# Keyboard_Mouse_Card.net
KiCad netlist of a schematic drawn in Altium Designer
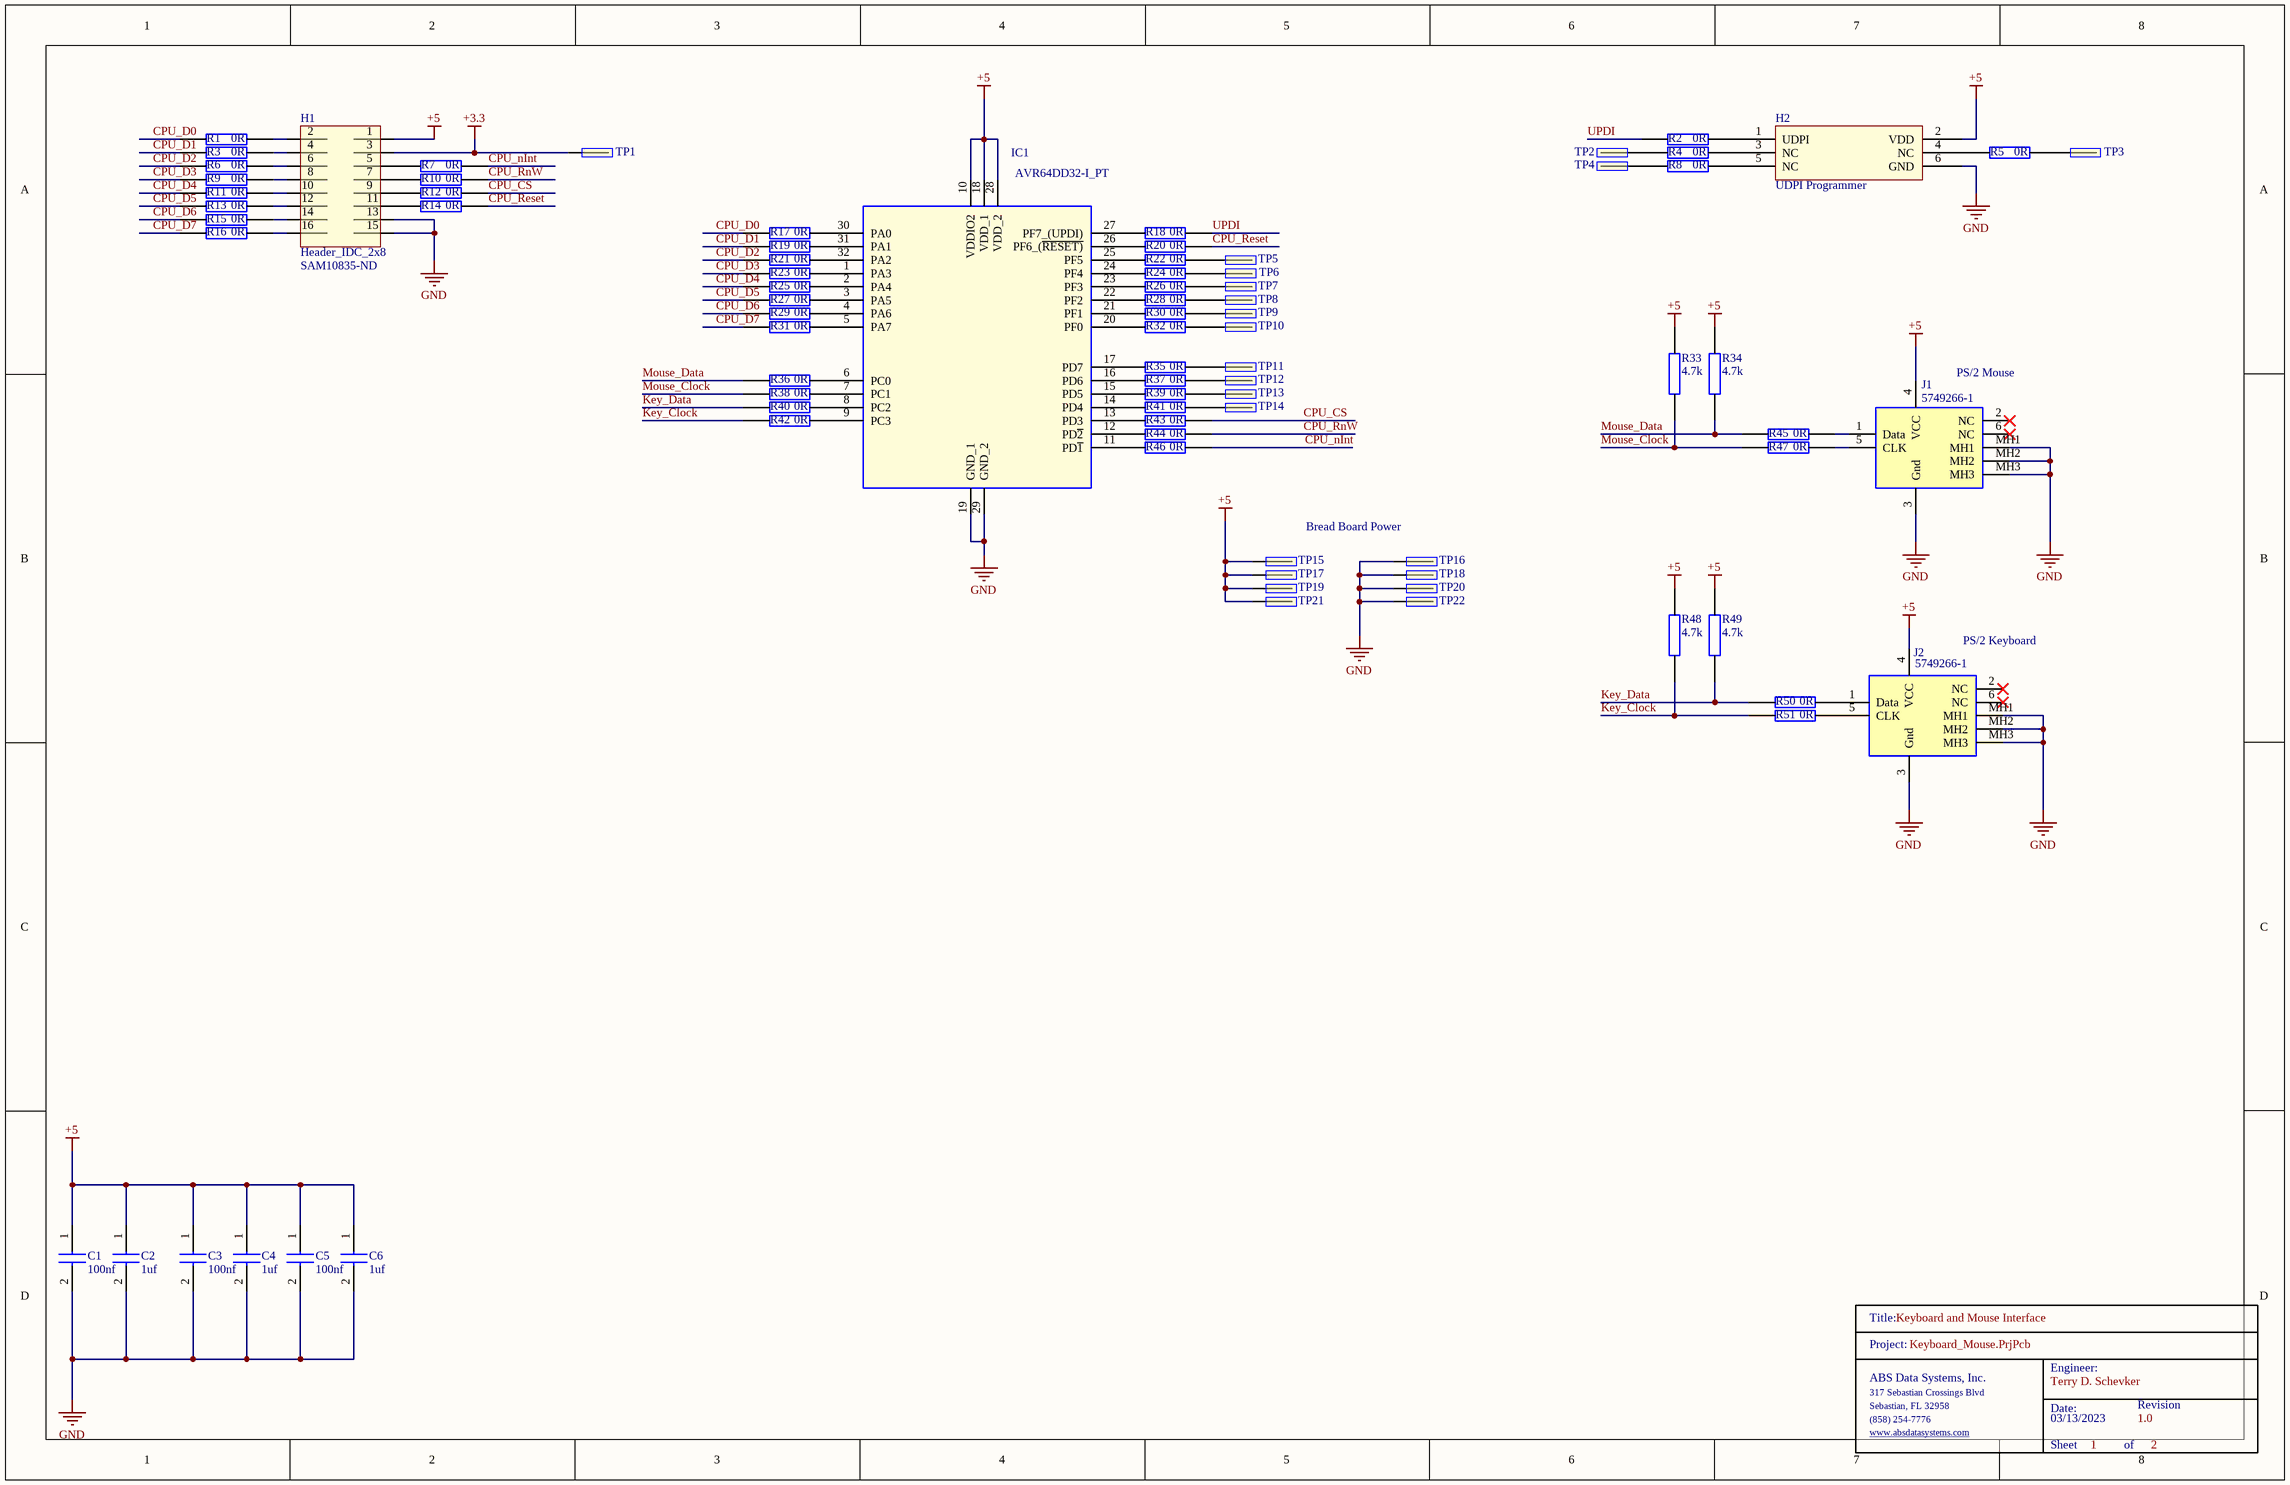
[diagram p0: Keyboard_Mouse_Card.SchDoc]

(export (version "E")
  (design (tool "Eeschema 10.0.6"))
  (components
    (comp (ref "C1")
      (value "100nf")
      (footprint "0603")
      (description "Samsung Electro-Mechanics 0603 100nf")
      (libsource (lib "Capacitors") (part "CL10B104JB8NNNC"))
    )
    (comp (ref "C2")
      (value "1uf")
      (footprint "0603")
      (description "Samsung Electro-Mechanics 0603 1uf")
      (libsource (lib "Capacitors") (part "CL10B105KA8NNNL"))
    )
    (comp (ref "C3")
      (value "100nf")
      (footprint "0603")
      (description "Samsung Electro-Mechanics 0603 100nf")
      (libsource (lib "Capacitors") (part "CL10B104JB8NNNC"))
    )
    (comp (ref "C4")
      (value "1uf")
      (footprint "0603")
      (description "Samsung Electro-Mechanics 0603 1uf")
      (libsource (lib "Capacitors") (part "CL10B105KA8NNNL"))
    )
    (comp (ref "C5")
      (value "100nf")
      (footprint "0603")
      (description "Samsung Electro-Mechanics 0603 100nf")
      (libsource (lib "Capacitors") (part "CL10B104JB8NNNC"))
    )
    (comp (ref "C6")
      (value "1uf")
      (footprint "0603")
      (description "Samsung Electro-Mechanics 0603 1uf")
      (libsource (lib "Capacitors") (part "CL10B105KA8NNNL"))
    )
    (comp (ref "H1")
      (value "Header_IDC_2x8")
      (footprint "HEADER16")
      (description "16 Pin 2x8 Through Hold IDC Connector")
      (fields
        (field (name "MANUFACTURER") "Samtec")
        (field (name "MANUFACTURER PART NUMBER") "TST-108-01-G-D")
        (field (name "SUPPLIER PART NUMBER 1") "SAM10835-ND")
      )
      (libsource (lib "Misc") (part "Header_IDC_2x8"))
    )
    (comp (ref "H2")
      (value "UDPI Programmer")
      (footprint "HDR2X3")
      (description "6 Pin 2X3 Through Hole Header")
      (libsource (lib "Misc") (part "UDPI Programmer"))
    )
    (comp (ref "IC1")
      (value "AVR64DD32-I_PT")
      (footprint "CPU_Memory:QFP80P900X900X120-32N")
      (description "Integrated Circuit")
      (fields (field (name "MANUFACTURER_PART_NUMBER") "AVR64DD32-I/PT ¦ MULTI-VOLTAGE I/O"))
      (libsource (lib "CPU_Memory") (part "AVR64DD32-I_PT"))
    )
    (comp (ref "J1")
      (value "5749266-1")
      (footprint "57492661")
      (description "Circular DIN Connectors 6 P R/A W/O HOLDDOWN")
      (fields (field (name "MOUSER PART NUMBER") "571-5749266-1"))
      (libsource (lib "Connectors") (part "5749266-1"))
    )
    (comp (ref "J2")
      (value "5749266-1")
      (footprint "57492661")
      (description "Circular DIN Connectors 6 P R/A W/O HOLDDOWN")
      (fields (field (name "MOUSER PART NUMBER") "571-5749266-1"))
      (libsource (lib "Connectors") (part "5749266-1"))
    )
    (comp (ref "R1")
      (value "0R")
      (footprint "0603")
      (description "YAGEO 0603 0 ohm")
      (fields
        (field (name "MOUSER PART NUMBER") "603-RC0603JR-070RL")
        (field (name "MANUFACTURER_PART_NUMBER") "RC0603JR-070RL")
      )
      (libsource (lib "Resistors") (part "RC0603JR-070RL"))
    )
    (comp (ref "R2")
      (value "0R")
      (footprint "0603")
      (description "YAGEO 0603 0 ohm")
      (fields
        (field (name "MOUSER PART NUMBER") "603-RC0603JR-070RL")
        (field (name "MANUFACTURER_PART_NUMBER") "RC0603JR-070RL")
      )
      (libsource (lib "Resistors") (part "RC0603JR-070RL"))
    )
    (comp (ref "R3")
      (value "0R")
      (footprint "0603")
      (description "YAGEO 0603 0 ohm")
      (fields
        (field (name "MOUSER PART NUMBER") "603-RC0603JR-070RL")
        (field (name "MANUFACTURER_PART_NUMBER") "RC0603JR-070RL")
      )
      (libsource (lib "Resistors") (part "RC0603JR-070RL"))
    )
    (comp (ref "R4")
      (value "0R")
      (footprint "0603")
      (description "YAGEO 0603 0 ohm")
      (fields
        (field (name "MOUSER PART NUMBER") "603-RC0603JR-070RL")
        (field (name "MANUFACTURER_PART_NUMBER") "RC0603JR-070RL")
      )
      (libsource (lib "Resistors") (part "RC0603JR-070RL"))
    )
    (comp (ref "R5")
      (value "0R")
      (footprint "0603")
      (description "YAGEO 0603 0 ohm")
      (fields
        (field (name "MOUSER PART NUMBER") "603-RC0603JR-070RL")
        (field (name "MANUFACTURER_PART_NUMBER") "RC0603JR-070RL")
      )
      (libsource (lib "Resistors") (part "RC0603JR-070RL"))
    )
    (comp (ref "R6")
      (value "0R")
      (footprint "0603")
      (description "YAGEO 0603 0 ohm")
      (fields
        (field (name "MOUSER PART NUMBER") "603-RC0603JR-070RL")
        (field (name "MANUFACTURER_PART_NUMBER") "RC0603JR-070RL")
      )
      (libsource (lib "Resistors") (part "RC0603JR-070RL"))
    )
    (comp (ref "R7")
      (value "0R")
      (footprint "0603")
      (description "YAGEO 0603 0 ohm")
      (fields
        (field (name "MOUSER PART NUMBER") "603-RC0603JR-070RL")
        (field (name "MANUFACTURER_PART_NUMBER") "RC0603JR-070RL")
      )
      (libsource (lib "Resistors") (part "RC0603JR-070RL"))
    )
    (comp (ref "R8")
      (value "0R")
      (footprint "0603")
      (description "YAGEO 0603 0 ohm")
      (fields
        (field (name "MOUSER PART NUMBER") "603-RC0603JR-070RL")
        (field (name "MANUFACTURER_PART_NUMBER") "RC0603JR-070RL")
      )
      (libsource (lib "Resistors") (part "RC0603JR-070RL"))
    )
    (comp (ref "R9")
      (value "0R")
      (footprint "0603")
      (description "YAGEO 0603 0 ohm")
      (fields
        (field (name "MOUSER PART NUMBER") "603-RC0603JR-070RL")
        (field (name "MANUFACTURER_PART_NUMBER") "RC0603JR-070RL")
      )
      (libsource (lib "Resistors") (part "RC0603JR-070RL"))
    )
    (comp (ref "R10")
      (value "0R")
      (footprint "0603")
      (description "YAGEO 0603 0 ohm")
      (fields
        (field (name "MOUSER PART NUMBER") "603-RC0603JR-070RL")
        (field (name "MANUFACTURER_PART_NUMBER") "RC0603JR-070RL")
      )
      (libsource (lib "Resistors") (part "RC0603JR-070RL"))
    )
    (comp (ref "R11")
      (value "0R")
      (footprint "0603")
      (description "YAGEO 0603 0 ohm")
      (fields
        (field (name "MOUSER PART NUMBER") "603-RC0603JR-070RL")
        (field (name "MANUFACTURER_PART_NUMBER") "RC0603JR-070RL")
      )
      (libsource (lib "Resistors") (part "RC0603JR-070RL"))
    )
    (comp (ref "R12")
      (value "0R")
      (footprint "0603")
      (description "YAGEO 0603 0 ohm")
      (fields
        (field (name "MOUSER PART NUMBER") "603-RC0603JR-070RL")
        (field (name "MANUFACTURER_PART_NUMBER") "RC0603JR-070RL")
      )
      (libsource (lib "Resistors") (part "RC0603JR-070RL"))
    )
    (comp (ref "R13")
      (value "0R")
      (footprint "0603")
      (description "YAGEO 0603 0 ohm")
      (fields
        (field (name "MOUSER PART NUMBER") "603-RC0603JR-070RL")
        (field (name "MANUFACTURER_PART_NUMBER") "RC0603JR-070RL")
      )
      (libsource (lib "Resistors") (part "RC0603JR-070RL"))
    )
    (comp (ref "R14")
      (value "0R")
      (footprint "0603")
      (description "YAGEO 0603 0 ohm")
      (fields
        (field (name "MOUSER PART NUMBER") "603-RC0603JR-070RL")
        (field (name "MANUFACTURER_PART_NUMBER") "RC0603JR-070RL")
      )
      (libsource (lib "Resistors") (part "RC0603JR-070RL"))
    )
    (comp (ref "R15")
      (value "0R")
      (footprint "0603")
      (description "YAGEO 0603 0 ohm")
      (fields
        (field (name "MOUSER PART NUMBER") "603-RC0603JR-070RL")
        (field (name "MANUFACTURER_PART_NUMBER") "RC0603JR-070RL")
      )
      (libsource (lib "Resistors") (part "RC0603JR-070RL"))
    )
    (comp (ref "R16")
      (value "0R")
      (footprint "0603")
      (description "YAGEO 0603 0 ohm")
      (fields
        (field (name "MOUSER PART NUMBER") "603-RC0603JR-070RL")
        (field (name "MANUFACTURER_PART_NUMBER") "RC0603JR-070RL")
      )
      (libsource (lib "Resistors") (part "RC0603JR-070RL"))
    )
    (comp (ref "R17")
      (value "0R")
      (footprint "0603")
      (description "YAGEO 0603 0 ohm")
      (fields
        (field (name "MOUSER PART NUMBER") "603-RC0603JR-070RL")
        (field (name "MANUFACTURER_PART_NUMBER") "RC0603JR-070RL")
      )
      (libsource (lib "Resistors") (part "RC0603JR-070RL"))
    )
    (comp (ref "R18")
      (value "0R")
      (footprint "0603")
      (description "YAGEO 0603 0 ohm")
      (fields
        (field (name "MOUSER PART NUMBER") "603-RC0603JR-070RL")
        (field (name "MANUFACTURER_PART_NUMBER") "RC0603JR-070RL")
      )
      (libsource (lib "Resistors") (part "RC0603JR-070RL"))
    )
    (comp (ref "R19")
      (value "0R")
      (footprint "0603")
      (description "YAGEO 0603 0 ohm")
      (fields
        (field (name "MOUSER PART NUMBER") "603-RC0603JR-070RL")
        (field (name "MANUFACTURER_PART_NUMBER") "RC0603JR-070RL")
      )
      (libsource (lib "Resistors") (part "RC0603JR-070RL"))
    )
    (comp (ref "R20")
      (value "0R")
      (footprint "0603")
      (description "YAGEO 0603 0 ohm")
      (fields
        (field (name "MOUSER PART NUMBER") "603-RC0603JR-070RL")
        (field (name "MANUFACTURER_PART_NUMBER") "RC0603JR-070RL")
      )
      (libsource (lib "Resistors") (part "RC0603JR-070RL"))
    )
    (comp (ref "R21")
      (value "0R")
      (footprint "0603")
      (description "YAGEO 0603 0 ohm")
      (fields
        (field (name "MOUSER PART NUMBER") "603-RC0603JR-070RL")
        (field (name "MANUFACTURER_PART_NUMBER") "RC0603JR-070RL")
      )
      (libsource (lib "Resistors") (part "RC0603JR-070RL"))
    )
    (comp (ref "R22")
      (value "0R")
      (footprint "0603")
      (description "YAGEO 0603 0 ohm")
      (fields
        (field (name "MOUSER PART NUMBER") "603-RC0603JR-070RL")
        (field (name "MANUFACTURER_PART_NUMBER") "RC0603JR-070RL")
      )
      (libsource (lib "Resistors") (part "RC0603JR-070RL"))
    )
    (comp (ref "R23")
      (value "0R")
      (footprint "0603")
      (description "YAGEO 0603 0 ohm")
      (fields
        (field (name "MOUSER PART NUMBER") "603-RC0603JR-070RL")
        (field (name "MANUFACTURER_PART_NUMBER") "RC0603JR-070RL")
      )
      (libsource (lib "Resistors") (part "RC0603JR-070RL"))
    )
    (comp (ref "R24")
      (value "0R")
      (footprint "0603")
      (description "YAGEO 0603 0 ohm")
      (fields
        (field (name "MOUSER PART NUMBER") "603-RC0603JR-070RL")
        (field (name "MANUFACTURER_PART_NUMBER") "RC0603JR-070RL")
      )
      (libsource (lib "Resistors") (part "RC0603JR-070RL"))
    )
    (comp (ref "R25")
      (value "0R")
      (footprint "0603")
      (description "YAGEO 0603 0 ohm")
      (fields
        (field (name "MOUSER PART NUMBER") "603-RC0603JR-070RL")
        (field (name "MANUFACTURER_PART_NUMBER") "RC0603JR-070RL")
      )
      (libsource (lib "Resistors") (part "RC0603JR-070RL"))
    )
    (comp (ref "R26")
      (value "0R")
      (footprint "0603")
      (description "YAGEO 0603 0 ohm")
      (fields
        (field (name "MOUSER PART NUMBER") "603-RC0603JR-070RL")
        (field (name "MANUFACTURER_PART_NUMBER") "RC0603JR-070RL")
      )
      (libsource (lib "Resistors") (part "RC0603JR-070RL"))
    )
    (comp (ref "R27")
      (value "0R")
      (footprint "0603")
      (description "YAGEO 0603 0 ohm")
      (fields
        (field (name "MOUSER PART NUMBER") "603-RC0603JR-070RL")
        (field (name "MANUFACTURER_PART_NUMBER") "RC0603JR-070RL")
      )
      (libsource (lib "Resistors") (part "RC0603JR-070RL"))
    )
    (comp (ref "R28")
      (value "0R")
      (footprint "0603")
      (description "YAGEO 0603 0 ohm")
      (fields
        (field (name "MOUSER PART NUMBER") "603-RC0603JR-070RL")
        (field (name "MANUFACTURER_PART_NUMBER") "RC0603JR-070RL")
      )
      (libsource (lib "Resistors") (part "RC0603JR-070RL"))
    )
    (comp (ref "R29")
      (value "0R")
      (footprint "0603")
      (description "YAGEO 0603 0 ohm")
      (fields
        (field (name "MOUSER PART NUMBER") "603-RC0603JR-070RL")
        (field (name "MANUFACTURER_PART_NUMBER") "RC0603JR-070RL")
      )
      (libsource (lib "Resistors") (part "RC0603JR-070RL"))
    )
    (comp (ref "R30")
      (value "0R")
      (footprint "0603")
      (description "YAGEO 0603 0 ohm")
      (fields
        (field (name "MOUSER PART NUMBER") "603-RC0603JR-070RL")
        (field (name "MANUFACTURER_PART_NUMBER") "RC0603JR-070RL")
      )
      (libsource (lib "Resistors") (part "RC0603JR-070RL"))
    )
    (comp (ref "R31")
      (value "0R")
      (footprint "0603")
      (description "YAGEO 0603 0 ohm")
      (fields
        (field (name "MOUSER PART NUMBER") "603-RC0603JR-070RL")
        (field (name "MANUFACTURER_PART_NUMBER") "RC0603JR-070RL")
      )
      (libsource (lib "Resistors") (part "RC0603JR-070RL"))
    )
    (comp (ref "R32")
      (value "0R")
      (footprint "0603")
      (description "YAGEO 0603 0 ohm")
      (fields
        (field (name "MOUSER PART NUMBER") "603-RC0603JR-070RL")
        (field (name "MANUFACTURER_PART_NUMBER") "RC0603JR-070RL")
      )
      (libsource (lib "Resistors") (part "RC0603JR-070RL"))
    )
    (comp (ref "R33")
      (value "4.7k")
      (footprint "0603")
      (description "YAGEO 0603 4.7k")
      (fields
        (field (name "MOUSER PART NUMBER") "603-RC0603JR-070RL")
        (field (name "MANUFACTURER_PART_NUMBER") "RC0603JR-070RL")
      )
      (libsource (lib "Resistors") (part "RC0603FR-104K7L"))
    )
    (comp (ref "R34")
      (value "4.7k")
      (footprint "0603")
      (description "YAGEO 0603 4.7k")
      (fields
        (field (name "MOUSER PART NUMBER") "603-RC0603JR-070RL")
        (field (name "MANUFACTURER_PART_NUMBER") "RC0603JR-070RL")
      )
      (libsource (lib "Resistors") (part "RC0603FR-104K7L"))
    )
    (comp (ref "R35")
      (value "0R")
      (footprint "0603")
      (description "YAGEO 0603 0 ohm")
      (fields
        (field (name "MOUSER PART NUMBER") "603-RC0603JR-070RL")
        (field (name "MANUFACTURER_PART_NUMBER") "RC0603JR-070RL")
      )
      (libsource (lib "Resistors") (part "RC0603JR-070RL"))
    )
    (comp (ref "R36")
      (value "0R")
      (footprint "0603")
      (description "YAGEO 0603 0 ohm")
      (fields
        (field (name "MOUSER PART NUMBER") "603-RC0603JR-070RL")
        (field (name "MANUFACTURER_PART_NUMBER") "RC0603JR-070RL")
      )
      (libsource (lib "Resistors") (part "RC0603JR-070RL"))
    )
    (comp (ref "R37")
      (value "0R")
      (footprint "0603")
      (description "YAGEO 0603 0 ohm")
      (fields
        (field (name "MOUSER PART NUMBER") "603-RC0603JR-070RL")
        (field (name "MANUFACTURER_PART_NUMBER") "RC0603JR-070RL")
      )
      (libsource (lib "Resistors") (part "RC0603JR-070RL"))
    )
    (comp (ref "R38")
      (value "0R")
      (footprint "0603")
      (description "YAGEO 0603 0 ohm")
      (fields
        (field (name "MOUSER PART NUMBER") "603-RC0603JR-070RL")
        (field (name "MANUFACTURER_PART_NUMBER") "RC0603JR-070RL")
      )
      (libsource (lib "Resistors") (part "RC0603JR-070RL"))
    )
    (comp (ref "R39")
      (value "0R")
      (footprint "0603")
      (description "YAGEO 0603 0 ohm")
      (fields
        (field (name "MOUSER PART NUMBER") "603-RC0603JR-070RL")
        (field (name "MANUFACTURER_PART_NUMBER") "RC0603JR-070RL")
      )
      (libsource (lib "Resistors") (part "RC0603JR-070RL"))
    )
    (comp (ref "R40")
      (value "0R")
      (footprint "0603")
      (description "YAGEO 0603 0 ohm")
      (fields
        (field (name "MOUSER PART NUMBER") "603-RC0603JR-070RL")
        (field (name "MANUFACTURER_PART_NUMBER") "RC0603JR-070RL")
      )
      (libsource (lib "Resistors") (part "RC0603JR-070RL"))
    )
    (comp (ref "R41")
      (value "0R")
      (footprint "0603")
      (description "YAGEO 0603 0 ohm")
      (fields
        (field (name "MOUSER PART NUMBER") "603-RC0603JR-070RL")
        (field (name "MANUFACTURER_PART_NUMBER") "RC0603JR-070RL")
      )
      (libsource (lib "Resistors") (part "RC0603JR-070RL"))
    )
    (comp (ref "R42")
      (value "0R")
      (footprint "0603")
      (description "YAGEO 0603 0 ohm")
      (fields
        (field (name "MOUSER PART NUMBER") "603-RC0603JR-070RL")
        (field (name "MANUFACTURER_PART_NUMBER") "RC0603JR-070RL")
      )
      (libsource (lib "Resistors") (part "RC0603JR-070RL"))
    )
    (comp (ref "R43")
      (value "0R")
      (footprint "0603")
      (description "YAGEO 0603 0 ohm")
      (fields
        (field (name "MOUSER PART NUMBER") "603-RC0603JR-070RL")
        (field (name "MANUFACTURER_PART_NUMBER") "RC0603JR-070RL")
      )
      (libsource (lib "Resistors") (part "RC0603JR-070RL"))
    )
    (comp (ref "R44")
      (value "0R")
      (footprint "0603")
      (description "YAGEO 0603 0 ohm")
      (fields
        (field (name "MOUSER PART NUMBER") "603-RC0603JR-070RL")
        (field (name "MANUFACTURER_PART_NUMBER") "RC0603JR-070RL")
      )
      (libsource (lib "Resistors") (part "RC0603JR-070RL"))
    )
    (comp (ref "R45")
      (value "0R")
      (footprint "0603")
      (description "YAGEO 0603 0 ohm")
      (fields
        (field (name "MOUSER PART NUMBER") "603-RC0603JR-070RL")
        (field (name "MANUFACTURER_PART_NUMBER") "RC0603JR-070RL")
      )
      (libsource (lib "Resistors") (part "RC0603JR-070RL"))
    )
    (comp (ref "R46")
      (value "0R")
      (footprint "0603")
      (description "YAGEO 0603 0 ohm")
      (fields
        (field (name "MOUSER PART NUMBER") "603-RC0603JR-070RL")
        (field (name "MANUFACTURER_PART_NUMBER") "RC0603JR-070RL")
      )
      (libsource (lib "Resistors") (part "RC0603JR-070RL"))
    )
    (comp (ref "R47")
      (value "0R")
      (footprint "0603")
      (description "YAGEO 0603 0 ohm")
      (fields
        (field (name "MOUSER PART NUMBER") "603-RC0603JR-070RL")
        (field (name "MANUFACTURER_PART_NUMBER") "RC0603JR-070RL")
      )
      (libsource (lib "Resistors") (part "RC0603JR-070RL"))
    )
    (comp (ref "R48")
      (value "4.7k")
      (footprint "0603")
      (description "YAGEO 0603 4.7k")
      (fields
        (field (name "MOUSER PART NUMBER") "603-RC0603JR-070RL")
        (field (name "MANUFACTURER_PART_NUMBER") "RC0603JR-070RL")
      )
      (libsource (lib "Resistors") (part "RC0603FR-104K7L"))
    )
    (comp (ref "R49")
      (value "4.7k")
      (footprint "0603")
      (description "YAGEO 0603 4.7k")
      (fields
        (field (name "MOUSER PART NUMBER") "603-RC0603JR-070RL")
        (field (name "MANUFACTURER_PART_NUMBER") "RC0603JR-070RL")
      )
      (libsource (lib "Resistors") (part "RC0603FR-104K7L"))
    )
    (comp (ref "R50")
      (value "0R")
      (footprint "0603")
      (description "YAGEO 0603 0 ohm")
      (fields
        (field (name "MOUSER PART NUMBER") "603-RC0603JR-070RL")
        (field (name "MANUFACTURER_PART_NUMBER") "RC0603JR-070RL")
      )
      (libsource (lib "Resistors") (part "RC0603JR-070RL"))
    )
    (comp (ref "R51")
      (value "0R")
      (footprint "0603")
      (description "YAGEO 0603 0 ohm")
      (fields
        (field (name "MOUSER PART NUMBER") "603-RC0603JR-070RL")
        (field (name "MANUFACTURER_PART_NUMBER") "RC0603JR-070RL")
      )
      (libsource (lib "Resistors") (part "RC0603JR-070RL"))
    )
    (comp (ref "TitleBlock_1") (value "TitleBlock") (libsource (lib "Misc") (part "TitleBlock")))
    (comp (ref "TP1")
      (value "TP")
      (footprint "TP")
      (fields
        (field (name "MANUFACTURER") "Samtec")
        (field (name "MANUFACTURER PART NUMBER") "TST-105-01-G-D")
      )
      (libsource (lib "Misc") (part "TP"))
    )
    (comp (ref "TP2")
      (value "TP")
      (footprint "TP")
      (fields
        (field (name "MANUFACTURER") "Samtec")
        (field (name "MANUFACTURER PART NUMBER") "TST-105-01-G-D")
      )
      (libsource (lib "") (part "TP_1"))
    )
    (comp (ref "TP3")
      (value "TP")
      (footprint "TP")
      (fields
        (field (name "MANUFACTURER") "Samtec")
        (field (name "MANUFACTURER PART NUMBER") "TST-105-01-G-D")
      )
      (libsource (lib "Misc") (part "TP"))
    )
    (comp (ref "TP4")
      (value "TP")
      (footprint "TP")
      (fields
        (field (name "MANUFACTURER") "Samtec")
        (field (name "MANUFACTURER PART NUMBER") "TST-105-01-G-D")
      )
      (libsource (lib "") (part "TP_1"))
    )
    (comp (ref "TP5")
      (value "TP")
      (footprint "TP")
      (fields
        (field (name "MANUFACTURER") "Samtec")
        (field (name "MANUFACTURER PART NUMBER") "TST-105-01-G-D")
      )
      (libsource (lib "Misc") (part "TP"))
    )
    (comp (ref "TP6")
      (value "TP")
      (footprint "TP")
      (fields
        (field (name "MANUFACTURER") "Samtec")
        (field (name "MANUFACTURER PART NUMBER") "TST-105-01-G-D")
      )
      (libsource (lib "Misc") (part "TP"))
    )
    (comp (ref "TP7")
      (value "TP")
      (footprint "TP")
      (fields
        (field (name "MANUFACTURER") "Samtec")
        (field (name "MANUFACTURER PART NUMBER") "TST-105-01-G-D")
      )
      (libsource (lib "Misc") (part "TP"))
    )
    (comp (ref "TP8")
      (value "TP")
      (footprint "TP")
      (fields
        (field (name "MANUFACTURER") "Samtec")
        (field (name "MANUFACTURER PART NUMBER") "TST-105-01-G-D")
      )
      (libsource (lib "Misc") (part "TP"))
    )
    (comp (ref "TP9")
      (value "TP")
      (footprint "TP")
      (fields
        (field (name "MANUFACTURER") "Samtec")
        (field (name "MANUFACTURER PART NUMBER") "TST-105-01-G-D")
      )
      (libsource (lib "Misc") (part "TP"))
    )
    (comp (ref "TP10")
      (value "TP")
      (footprint "TP")
      (fields
        (field (name "MANUFACTURER") "Samtec")
        (field (name "MANUFACTURER PART NUMBER") "TST-105-01-G-D")
      )
      (libsource (lib "Misc") (part "TP"))
    )
    (comp (ref "TP11")
      (value "TP")
      (footprint "TP")
      (fields
        (field (name "MANUFACTURER") "Samtec")
        (field (name "MANUFACTURER PART NUMBER") "TST-105-01-G-D")
      )
      (libsource (lib "Misc") (part "TP"))
    )
    (comp (ref "TP12")
      (value "TP")
      (footprint "TP")
      (fields
        (field (name "MANUFACTURER") "Samtec")
        (field (name "MANUFACTURER PART NUMBER") "TST-105-01-G-D")
      )
      (libsource (lib "Misc") (part "TP"))
    )
    (comp (ref "TP13")
      (value "TP")
      (footprint "TP")
      (fields
        (field (name "MANUFACTURER") "Samtec")
        (field (name "MANUFACTURER PART NUMBER") "TST-105-01-G-D")
      )
      (libsource (lib "Misc") (part "TP"))
    )
    (comp (ref "TP14")
      (value "TP")
      (footprint "TP")
      (fields
        (field (name "MANUFACTURER") "Samtec")
        (field (name "MANUFACTURER PART NUMBER") "TST-105-01-G-D")
      )
      (libsource (lib "Misc") (part "TP"))
    )
    (comp (ref "TP15")
      (value "TP")
      (footprint "TP")
      (fields
        (field (name "MANUFACTURER") "Samtec")
        (field (name "MANUFACTURER PART NUMBER") "TST-105-01-G-D")
      )
      (libsource (lib "Misc") (part "TP"))
    )
    (comp (ref "TP16")
      (value "TP")
      (footprint "TP")
      (fields
        (field (name "MANUFACTURER") "Samtec")
        (field (name "MANUFACTURER PART NUMBER") "TST-105-01-G-D")
      )
      (libsource (lib "Misc") (part "TP"))
    )
    (comp (ref "TP17")
      (value "TP")
      (footprint "TP")
      (fields
        (field (name "MANUFACTURER") "Samtec")
        (field (name "MANUFACTURER PART NUMBER") "TST-105-01-G-D")
      )
      (libsource (lib "Misc") (part "TP"))
    )
    (comp (ref "TP18")
      (value "TP")
      (footprint "TP")
      (fields
        (field (name "MANUFACTURER") "Samtec")
        (field (name "MANUFACTURER PART NUMBER") "TST-105-01-G-D")
      )
      (libsource (lib "Misc") (part "TP"))
    )
    (comp (ref "TP19")
      (value "TP")
      (footprint "TP")
      (fields
        (field (name "MANUFACTURER") "Samtec")
        (field (name "MANUFACTURER PART NUMBER") "TST-105-01-G-D")
      )
      (libsource (lib "Misc") (part "TP"))
    )
    (comp (ref "TP20")
      (value "TP")
      (footprint "TP")
      (fields
        (field (name "MANUFACTURER") "Samtec")
        (field (name "MANUFACTURER PART NUMBER") "TST-105-01-G-D")
      )
      (libsource (lib "Misc") (part "TP"))
    )
    (comp (ref "TP21")
      (value "TP")
      (footprint "TP")
      (fields
        (field (name "MANUFACTURER") "Samtec")
        (field (name "MANUFACTURER PART NUMBER") "TST-105-01-G-D")
      )
      (libsource (lib "Misc") (part "TP"))
    )
    (comp (ref "TP22")
      (value "TP")
      (footprint "TP")
      (fields
        (field (name "MANUFACTURER") "Samtec")
        (field (name "MANUFACTURER PART NUMBER") "TST-105-01-G-D")
      )
      (libsource (lib "Misc") (part "TP"))
    )
  )
  (nets
    (net (code "1") (name "+3.3") (class "Default")
      (node (ref "H1") (pin "3") (pinfunction "3_3") (pintype "passive"))
      (node (ref "TP1") (pin "1") (pinfunction "1_1") (pintype "passive"))
    )
    (net (code "2") (name "+5") (class "Default")
      (node (ref "C1") (pin "1") (pinfunction "1_1") (pintype "passive"))
      (node (ref "C2") (pin "1") (pinfunction "1_1") (pintype "passive"))
      (node (ref "C3") (pin "1") (pinfunction "1_1") (pintype "passive"))
      (node (ref "C4") (pin "1") (pinfunction "1_1") (pintype "passive"))
      (node (ref "C5") (pin "1") (pinfunction "1_1") (pintype "passive"))
      (node (ref "C6") (pin "1") (pinfunction "1_1") (pintype "passive"))
      (node (ref "H1") (pin "1") (pinfunction "1_1") (pintype "passive"))
      (node (ref "H2") (pin "2") (pinfunction "VDD_2") (pintype "passive"))
      (node (ref "IC1") (pin "10") (pinfunction "VDDIO2_10") (pintype "passive"))
      (node (ref "IC1") (pin "18") (pinfunction "VDD_1_18") (pintype "passive"))
      (node (ref "IC1") (pin "28") (pinfunction "VDD_2_28") (pintype "passive"))
      (node (ref "J1") (pin "4") (pinfunction "VCC_4") (pintype "passive"))
      (node (ref "J2") (pin "4") (pinfunction "VCC_4") (pintype "passive"))
      (node (ref "R33") (pin "1") (pinfunction "1_1") (pintype "passive"))
      (node (ref "R34") (pin "1") (pinfunction "1_1") (pintype "passive"))
      (node (ref "R48") (pin "1") (pinfunction "1_1") (pintype "passive"))
      (node (ref "R49") (pin "1") (pinfunction "1_1") (pintype "passive"))
      (node (ref "TP15") (pin "1") (pinfunction "1_1") (pintype "passive"))
      (node (ref "TP17") (pin "1") (pinfunction "1_1") (pintype "passive"))
      (node (ref "TP19") (pin "1") (pinfunction "1_1") (pintype "passive"))
      (node (ref "TP21") (pin "1") (pinfunction "1_1") (pintype "passive"))
    )
    (net (code "3") (name "/CPU_CS") (class "Default")
      (node (ref "R12") (pin "2") (pinfunction "2_2") (pintype "passive"))
      (node (ref "R43") (pin "2") (pinfunction "2_2") (pintype "passive"))
    )
    (net (code "4") (name "/CPU_D0") (class "Default")
      (node (ref "R1") (pin "1") (pinfunction "1_1") (pintype "passive"))
      (node (ref "R17") (pin "1") (pinfunction "1_1") (pintype "passive"))
    )
    (net (code "5") (name "/CPU_D1") (class "Default")
      (node (ref "R19") (pin "1") (pinfunction "1_1") (pintype "passive"))
      (node (ref "R3") (pin "1") (pinfunction "1_1") (pintype "passive"))
    )
    (net (code "6") (name "/CPU_D2") (class "Default")
      (node (ref "R21") (pin "1") (pinfunction "1_1") (pintype "passive"))
      (node (ref "R6") (pin "1") (pinfunction "1_1") (pintype "passive"))
    )
    (net (code "7") (name "/CPU_D3") (class "Default")
      (node (ref "R23") (pin "1") (pinfunction "1_1") (pintype "passive"))
      (node (ref "R9") (pin "1") (pinfunction "1_1") (pintype "passive"))
    )
    (net (code "8") (name "/CPU_D4") (class "Default")
      (node (ref "R11") (pin "1") (pinfunction "1_1") (pintype "passive"))
      (node (ref "R25") (pin "1") (pinfunction "1_1") (pintype "passive"))
    )
    (net (code "9") (name "/CPU_D5") (class "Default")
      (node (ref "R13") (pin "1") (pinfunction "1_1") (pintype "passive"))
      (node (ref "R27") (pin "1") (pinfunction "1_1") (pintype "passive"))
    )
    (net (code "10") (name "/CPU_D6") (class "Default")
      (node (ref "R15") (pin "1") (pinfunction "1_1") (pintype "passive"))
      (node (ref "R29") (pin "1") (pinfunction "1_1") (pintype "passive"))
    )
    (net (code "11") (name "/CPU_D7") (class "Default")
      (node (ref "R16") (pin "1") (pinfunction "1_1") (pintype "passive"))
      (node (ref "R31") (pin "1") (pinfunction "1_1") (pintype "passive"))
    )
    (net (code "12") (name "/CPU_Reset") (class "Default")
      (node (ref "R14") (pin "2") (pinfunction "2_2") (pintype "passive"))
      (node (ref "R20") (pin "2") (pinfunction "2_2") (pintype "passive"))
    )
    (net (code "13") (name "/CPU_RnW") (class "Default")
      (node (ref "R10") (pin "2") (pinfunction "2_2") (pintype "passive"))
      (node (ref "R44") (pin "2") (pinfunction "2_2") (pintype "passive"))
    )
    (net (code "14") (name "/CPU_nInt") (class "Default")
      (node (ref "R46") (pin "2") (pinfunction "2_2") (pintype "passive"))
      (node (ref "R7") (pin "2") (pinfunction "2_2") (pintype "passive"))
    )
    (net (code "15") (name "/Key_Clock") (class "Default")
      (node (ref "R42") (pin "1") (pinfunction "1_1") (pintype "passive"))
      (node (ref "R48") (pin "2") (pinfunction "2_2") (pintype "passive"))
      (node (ref "R51") (pin "1") (pinfunction "1_1") (pintype "passive"))
    )
    (net (code "16") (name "/Key_Data") (class "Default")
      (node (ref "R40") (pin "1") (pinfunction "1_1") (pintype "passive"))
      (node (ref "R49") (pin "2") (pinfunction "2_2") (pintype "passive"))
      (node (ref "R50") (pin "1") (pinfunction "1_1") (pintype "passive"))
    )
    (net (code "17") (name "/Mouse_Clock") (class "Default")
      (node (ref "R33") (pin "2") (pinfunction "2_2") (pintype "passive"))
      (node (ref "R38") (pin "1") (pinfunction "1_1") (pintype "passive"))
      (node (ref "R47") (pin "1") (pinfunction "1_1") (pintype "passive"))
    )
    (net (code "18") (name "/Mouse_Data") (class "Default")
      (node (ref "R34") (pin "2") (pinfunction "2_2") (pintype "passive"))
      (node (ref "R36") (pin "1") (pinfunction "1_1") (pintype "passive"))
      (node (ref "R45") (pin "1") (pinfunction "1_1") (pintype "passive"))
    )
    (net (code "19") (name "/UPDI") (class "Default")
      (node (ref "R18") (pin "2") (pinfunction "2_2") (pintype "passive"))
      (node (ref "R2") (pin "1") (pinfunction "1_1") (pintype "passive"))
    )
    (net (code "20") (name "GND") (class "Default")
      (node (ref "C1") (pin "2") (pinfunction "2_2") (pintype "passive"))
      (node (ref "C2") (pin "2") (pinfunction "2_2") (pintype "passive"))
      (node (ref "C3") (pin "2") (pinfunction "2_2") (pintype "passive"))
      (node (ref "C4") (pin "2") (pinfunction "2_2") (pintype "passive"))
      (node (ref "C5") (pin "2") (pinfunction "2_2") (pintype "passive"))
      (node (ref "C6") (pin "2") (pinfunction "2_2") (pintype "passive"))
      (node (ref "H1") (pin "13") (pinfunction "13_13") (pintype "passive"))
      (node (ref "H1") (pin "15") (pinfunction "15_15") (pintype "passive"))
      (node (ref "H2") (pin "6") (pinfunction "GND_6") (pintype "passive"))
      (node (ref "IC1") (pin "19") (pinfunction "GND_1_19") (pintype "passive"))
      (node (ref "IC1") (pin "29") (pinfunction "GND_2_29") (pintype "passive"))
      (node (ref "J1") (pin "3") (pinfunction "Gnd_3") (pintype "passive"))
      (node (ref "J1") (pin "MH1") (pinfunction "MH1_MH1") (pintype "passive"))
      (node (ref "J1") (pin "MH2") (pinfunction "MH2_MH2") (pintype "passive"))
      (node (ref "J1") (pin "MH3") (pinfunction "MH3_MH3") (pintype "passive"))
      (node (ref "J2") (pin "3") (pinfunction "Gnd_3") (pintype "passive"))
      (node (ref "J2") (pin "MH1") (pinfunction "MH1_MH1") (pintype "passive"))
      (node (ref "J2") (pin "MH2") (pinfunction "MH2_MH2") (pintype "passive"))
      (node (ref "J2") (pin "MH3") (pinfunction "MH3_MH3") (pintype "passive"))
      (node (ref "TP16") (pin "1") (pinfunction "1_1") (pintype "passive"))
      (node (ref "TP18") (pin "1") (pinfunction "1_1") (pintype "passive"))
      (node (ref "TP20") (pin "1") (pinfunction "1_1") (pintype "passive"))
      (node (ref "TP22") (pin "1") (pinfunction "1_1") (pintype "passive"))
    )
    (net (code "21") (name "Net-(H1-Pad2)") (class "Default")
      (node (ref "H1") (pin "2") (pinfunction "2_2") (pintype "passive"))
      (node (ref "R1") (pin "2") (pinfunction "2_2") (pintype "passive"))
    )
    (net (code "22") (name "Net-(H1-Pad4)") (class "Default")
      (node (ref "H1") (pin "4") (pinfunction "4_4") (pintype "passive"))
      (node (ref "R3") (pin "2") (pinfunction "2_2") (pintype "passive"))
    )
    (net (code "23") (name "Net-(H1-Pad5)") (class "Default")
      (node (ref "H1") (pin "5") (pinfunction "5_5") (pintype "passive"))
      (node (ref "R7") (pin "1") (pinfunction "1_1") (pintype "passive"))
    )
    (net (code "24") (name "Net-(H1-Pad6)") (class "Default")
      (node (ref "H1") (pin "6") (pinfunction "6_6") (pintype "passive"))
      (node (ref "R6") (pin "2") (pinfunction "2_2") (pintype "passive"))
    )
    (net (code "25") (name "Net-(H1-Pad7)") (class "Default")
      (node (ref "H1") (pin "7") (pinfunction "7_7") (pintype "passive"))
      (node (ref "R10") (pin "1") (pinfunction "1_1") (pintype "passive"))
    )
    (net (code "26") (name "Net-(H1-Pad8)") (class "Default")
      (node (ref "H1") (pin "8") (pinfunction "8_8") (pintype "passive"))
      (node (ref "R9") (pin "2") (pinfunction "2_2") (pintype "passive"))
    )
    (net (code "27") (name "Net-(H1-Pad9)") (class "Default")
      (node (ref "H1") (pin "9") (pinfunction "9_9") (pintype "passive"))
      (node (ref "R12") (pin "1") (pinfunction "1_1") (pintype "passive"))
    )
    (net (code "28") (name "Net-(H1-Pad10)") (class "Default")
      (node (ref "H1") (pin "10") (pinfunction "10_10") (pintype "passive"))
      (node (ref "R11") (pin "2") (pinfunction "2_2") (pintype "passive"))
    )
    (net (code "29") (name "Net-(H1-Pad11)") (class "Default")
      (node (ref "H1") (pin "11") (pinfunction "11_11") (pintype "passive"))
      (node (ref "R14") (pin "1") (pinfunction "1_1") (pintype "passive"))
    )
    (net (code "30") (name "Net-(H1-Pad12)") (class "Default")
      (node (ref "H1") (pin "12") (pinfunction "12_12") (pintype "passive"))
      (node (ref "R13") (pin "2") (pinfunction "2_2") (pintype "passive"))
    )
    (net (code "31") (name "Net-(H1-Pad14)") (class "Default")
      (node (ref "H1") (pin "14") (pinfunction "14_14") (pintype "passive"))
      (node (ref "R15") (pin "2") (pinfunction "2_2") (pintype "passive"))
    )
    (net (code "32") (name "Net-(H1-Pad16)") (class "Default")
      (node (ref "H1") (pin "16") (pinfunction "16_16") (pintype "passive"))
      (node (ref "R16") (pin "2") (pinfunction "2_2") (pintype "passive"))
    )
    (net (code "33") (name "Net-(H2-NC-Pad3)") (class "Default")
      (node (ref "H2") (pin "3") (pinfunction "NC_3") (pintype "passive"))
      (node (ref "R4") (pin "2") (pinfunction "2_2") (pintype "passive"))
    )
    (net (code "34") (name "Net-(H2-NC-Pad4)") (class "Default")
      (node (ref "H2") (pin "4") (pinfunction "NC_4") (pintype "passive"))
      (node (ref "R5") (pin "1") (pinfunction "1_1") (pintype "passive"))
    )
    (net (code "35") (name "Net-(H2-NC-Pad5)") (class "Default")
      (node (ref "H2") (pin "5") (pinfunction "NC_5") (pintype "passive"))
      (node (ref "R8") (pin "2") (pinfunction "2_2") (pintype "passive"))
    )
    (net (code "36") (name "Net-(H2-UDPI)") (class "Default")
      (node (ref "H2") (pin "1") (pinfunction "UDPI_1") (pintype "passive"))
      (node (ref "R2") (pin "2") (pinfunction "2_2") (pintype "passive"))
    )
    (net (code "37") (name "Net-(IC1-PA0)") (class "Default")
      (node (ref "IC1") (pin "30") (pinfunction "PA0_30") (pintype "passive"))
      (node (ref "R17") (pin "2") (pinfunction "2_2") (pintype "passive"))
    )
    (net (code "38") (name "Net-(IC1-PA1)") (class "Default")
      (node (ref "IC1") (pin "31") (pinfunction "PA1_31") (pintype "passive"))
      (node (ref "R19") (pin "2") (pinfunction "2_2") (pintype "passive"))
    )
    (net (code "39") (name "Net-(IC1-PA2)") (class "Default")
      (node (ref "IC1") (pin "32") (pinfunction "PA2_32") (pintype "passive"))
      (node (ref "R21") (pin "2") (pinfunction "2_2") (pintype "passive"))
    )
    (net (code "40") (name "Net-(IC1-PA3)") (class "Default")
      (node (ref "IC1") (pin "1") (pinfunction "PA3_1") (pintype "passive"))
      (node (ref "R23") (pin "2") (pinfunction "2_2") (pintype "passive"))
    )
    (net (code "41") (name "Net-(IC1-PA4)") (class "Default")
      (node (ref "IC1") (pin "2") (pinfunction "PA4_2") (pintype "passive"))
      (node (ref "R25") (pin "2") (pinfunction "2_2") (pintype "passive"))
    )
    (net (code "42") (name "Net-(IC1-PA5)") (class "Default")
      (node (ref "IC1") (pin "3") (pinfunction "PA5_3") (pintype "passive"))
      (node (ref "R27") (pin "2") (pinfunction "2_2") (pintype "passive"))
    )
    (net (code "43") (name "Net-(IC1-PA6)") (class "Default")
      (node (ref "IC1") (pin "4") (pinfunction "PA6_4") (pintype "passive"))
      (node (ref "R29") (pin "2") (pinfunction "2_2") (pintype "passive"))
    )
    (net (code "44") (name "Net-(IC1-PA7)") (class "Default")
      (node (ref "IC1") (pin "5") (pinfunction "PA7_5") (pintype "passive"))
      (node (ref "R31") (pin "2") (pinfunction "2_2") (pintype "passive"))
    )
    (net (code "45") (name "Net-(IC1-PC0)") (class "Default")
      (node (ref "IC1") (pin "6") (pinfunction "PC0_6") (pintype "passive"))
      (node (ref "R36") (pin "2") (pinfunction "2_2") (pintype "passive"))
    )
    (net (code "46") (name "Net-(IC1-PC1)") (class "Default")
      (node (ref "IC1") (pin "7") (pinfunction "PC1_7") (pintype "passive"))
      (node (ref "R38") (pin "2") (pinfunction "2_2") (pintype "passive"))
    )
    (net (code "47") (name "Net-(IC1-PC2)") (class "Default")
      (node (ref "IC1") (pin "8") (pinfunction "PC2_8") (pintype "passive"))
      (node (ref "R40") (pin "2") (pinfunction "2_2") (pintype "passive"))
    )
    (net (code "48") (name "Net-(IC1-PC3)") (class "Default")
      (node (ref "IC1") (pin "9") (pinfunction "PC3_9") (pintype "passive"))
      (node (ref "R42") (pin "2") (pinfunction "2_2") (pintype "passive"))
    )
    (net (code "49") (name "Net-(IC1-PD3)") (class "Default")
      (node (ref "IC1") (pin "13") (pinfunction "PD3_13") (pintype "passive"))
      (node (ref "R43") (pin "1") (pinfunction "1_1") (pintype "passive"))
    )
    (net (code "50") (name "Net-(IC1-PD4)") (class "Default")
      (node (ref "IC1") (pin "14") (pinfunction "PD4_14") (pintype "passive"))
      (node (ref "R41") (pin "1") (pinfunction "1_1") (pintype "passive"))
    )
    (net (code "51") (name "Net-(IC1-PD5)") (class "Default")
      (node (ref "IC1") (pin "15") (pinfunction "PD5_15") (pintype "passive"))
      (node (ref "R39") (pin "1") (pinfunction "1_1") (pintype "passive"))
    )
    (net (code "52") (name "Net-(IC1-PD6)") (class "Default")
      (node (ref "IC1") (pin "16") (pinfunction "PD6_16") (pintype "passive"))
      (node (ref "R37") (pin "1") (pinfunction "1_1") (pintype "passive"))
    )
    (net (code "53") (name "Net-(IC1-PD7)") (class "Default")
      (node (ref "IC1") (pin "17") (pinfunction "PD7_17") (pintype "passive"))
      (node (ref "R35") (pin "1") (pinfunction "1_1") (pintype "passive"))
    )
    (net (code "54") (name "Net-(IC1-PD~{1})") (class "Default")
      (node (ref "IC1") (pin "11") (pinfunction "PD~{1}_11") (pintype "passive"))
      (node (ref "R46") (pin "1") (pinfunction "1_1") (pintype "passive"))
    )
    (net (code "55") (name "Net-(IC1-PD~{2})") (class "Default")
      (node (ref "IC1") (pin "12") (pinfunction "PD~{2}_12") (pintype "passive"))
      (node (ref "R44") (pin "1") (pinfunction "1_1") (pintype "passive"))
    )
    (net (code "56") (name "Net-(IC1-PF0)") (class "Default")
      (node (ref "IC1") (pin "20") (pinfunction "PF0_20") (pintype "passive"))
      (node (ref "R32") (pin "1") (pinfunction "1_1") (pintype "passive"))
    )
    (net (code "57") (name "Net-(IC1-PF1)") (class "Default")
      (node (ref "IC1") (pin "21") (pinfunction "PF1_21") (pintype "passive"))
      (node (ref "R30") (pin "1") (pinfunction "1_1") (pintype "passive"))
    )
    (net (code "58") (name "Net-(IC1-PF2)") (class "Default")
      (node (ref "IC1") (pin "22") (pinfunction "PF2_22") (pintype "passive"))
      (node (ref "R28") (pin "1") (pinfunction "1_1") (pintype "passive"))
    )
    (net (code "59") (name "Net-(IC1-PF3)") (class "Default")
      (node (ref "IC1") (pin "23") (pinfunction "PF3_23") (pintype "passive"))
      (node (ref "R26") (pin "1") (pinfunction "1_1") (pintype "passive"))
    )
    (net (code "60") (name "Net-(IC1-PF4)") (class "Default")
      (node (ref "IC1") (pin "24") (pinfunction "PF4_24") (pintype "passive"))
      (node (ref "R24") (pin "1") (pinfunction "1_1") (pintype "passive"))
    )
    (net (code "61") (name "Net-(IC1-PF5)") (class "Default")
      (node (ref "IC1") (pin "25") (pinfunction "PF5_25") (pintype "passive"))
      (node (ref "R22") (pin "1") (pinfunction "1_1") (pintype "passive"))
    )
    (net (code "62") (name "Net-(IC1-PF6_(~{RESET)})") (class "Default")
      (node (ref "IC1") (pin "26") (pinfunction "PF6_(~{RESET)}_26") (pintype "passive"))
      (node (ref "R20") (pin "1") (pinfunction "1_1") (pintype "passive"))
    )
    (net (code "63") (name "Net-(IC1-PF7_(UPDI))") (class "Default")
      (node (ref "IC1") (pin "27") (pinfunction "PF7_(UPDI)_27") (pintype "passive"))
      (node (ref "R18") (pin "1") (pinfunction "1_1") (pintype "passive"))
    )
    (net (code "64") (name "Net-(J1-CLK)") (class "Default")
      (node (ref "J1") (pin "5") (pinfunction "CLK_5") (pintype "passive"))
      (node (ref "R47") (pin "2") (pinfunction "2_2") (pintype "passive"))
    )
    (net (code "65") (name "Net-(J1-Data)") (class "Default")
      (node (ref "J1") (pin "1") (pinfunction "Data_1") (pintype "passive"))
      (node (ref "R45") (pin "2") (pinfunction "2_2") (pintype "passive"))
    )
    (net (code "66") (name "Net-(J2-CLK)") (class "Default")
      (node (ref "J2") (pin "5") (pinfunction "CLK_5") (pintype "passive"))
      (node (ref "R51") (pin "2") (pinfunction "2_2") (pintype "passive"))
    )
    (net (code "67") (name "Net-(J2-Data)") (class "Default")
      (node (ref "J2") (pin "1") (pinfunction "Data_1") (pintype "passive"))
      (node (ref "R50") (pin "2") (pinfunction "2_2") (pintype "passive"))
    )
    (net (code "68") (name "Net-(R4-Pad1)") (class "Default")
      (node (ref "R4") (pin "1") (pinfunction "1_1") (pintype "passive"))
      (node (ref "TP2") (pin "1") (pinfunction "1_1") (pintype "passive"))
    )
    (net (code "69") (name "Net-(R5-Pad2)") (class "Default")
      (node (ref "R5") (pin "2") (pinfunction "2_2") (pintype "passive"))
      (node (ref "TP3") (pin "1") (pinfunction "1_1") (pintype "passive"))
    )
    (net (code "70") (name "Net-(R8-Pad1)") (class "Default")
      (node (ref "R8") (pin "1") (pinfunction "1_1") (pintype "passive"))
      (node (ref "TP4") (pin "1") (pinfunction "1_1") (pintype "passive"))
    )
    (net (code "71") (name "Net-(R22-Pad2)") (class "Default")
      (node (ref "R22") (pin "2") (pinfunction "2_2") (pintype "passive"))
      (node (ref "TP5") (pin "1") (pinfunction "1_1") (pintype "passive"))
    )
    (net (code "72") (name "Net-(R24-Pad2)") (class "Default")
      (node (ref "R24") (pin "2") (pinfunction "2_2") (pintype "passive"))
      (node (ref "TP6") (pin "1") (pinfunction "1_1") (pintype "passive"))
    )
    (net (code "73") (name "Net-(R26-Pad2)") (class "Default")
      (node (ref "R26") (pin "2") (pinfunction "2_2") (pintype "passive"))
      (node (ref "TP7") (pin "1") (pinfunction "1_1") (pintype "passive"))
    )
    (net (code "74") (name "Net-(R28-Pad2)") (class "Default")
      (node (ref "R28") (pin "2") (pinfunction "2_2") (pintype "passive"))
      (node (ref "TP8") (pin "1") (pinfunction "1_1") (pintype "passive"))
    )
    (net (code "75") (name "Net-(R30-Pad2)") (class "Default")
      (node (ref "R30") (pin "2") (pinfunction "2_2") (pintype "passive"))
      (node (ref "TP9") (pin "1") (pinfunction "1_1") (pintype "passive"))
    )
    (net (code "76") (name "Net-(R32-Pad2)") (class "Default")
      (node (ref "R32") (pin "2") (pinfunction "2_2") (pintype "passive"))
      (node (ref "TP10") (pin "1") (pinfunction "1_1") (pintype "passive"))
    )
    (net (code "77") (name "Net-(R35-Pad2)") (class "Default")
      (node (ref "R35") (pin "2") (pinfunction "2_2") (pintype "passive"))
      (node (ref "TP11") (pin "1") (pinfunction "1_1") (pintype "passive"))
    )
    (net (code "78") (name "Net-(R37-Pad2)") (class "Default")
      (node (ref "R37") (pin "2") (pinfunction "2_2") (pintype "passive"))
      (node (ref "TP12") (pin "1") (pinfunction "1_1") (pintype "passive"))
    )
    (net (code "79") (name "Net-(R39-Pad2)") (class "Default")
      (node (ref "R39") (pin "2") (pinfunction "2_2") (pintype "passive"))
      (node (ref "TP13") (pin "1") (pinfunction "1_1") (pintype "passive"))
    )
    (net (code "80") (name "Net-(R41-Pad2)") (class "Default")
      (node (ref "R41") (pin "2") (pinfunction "2_2") (pintype "passive"))
      (node (ref "TP14") (pin "1") (pinfunction "1_1") (pintype "passive"))
    )
    (net (code "81") (name "unconnected-(J1-NC-Pad2)") (class "Default")
      (node (ref "J1") (pin "2") (pinfunction "NC_2") (pintype "passive+no_connect"))
    )
    (net (code "82") (name "unconnected-(J1-NC-Pad6)") (class "Default")
      (node (ref "J1") (pin "6") (pinfunction "NC_6") (pintype "passive+no_connect"))
    )
    (net (code "83") (name "unconnected-(J2-NC-Pad2)") (class "Default")
      (node (ref "J2") (pin "2") (pinfunction "NC_2") (pintype "passive+no_connect"))
    )
    (net (code "84") (name "unconnected-(J2-NC-Pad6)") (class "Default")
      (node (ref "J2") (pin "6") (pinfunction "NC_6") (pintype "passive+no_connect"))
    )
  )
)
